# smps_v_1_3.net
KiCad netlist of a schematic drawn in EAGLE
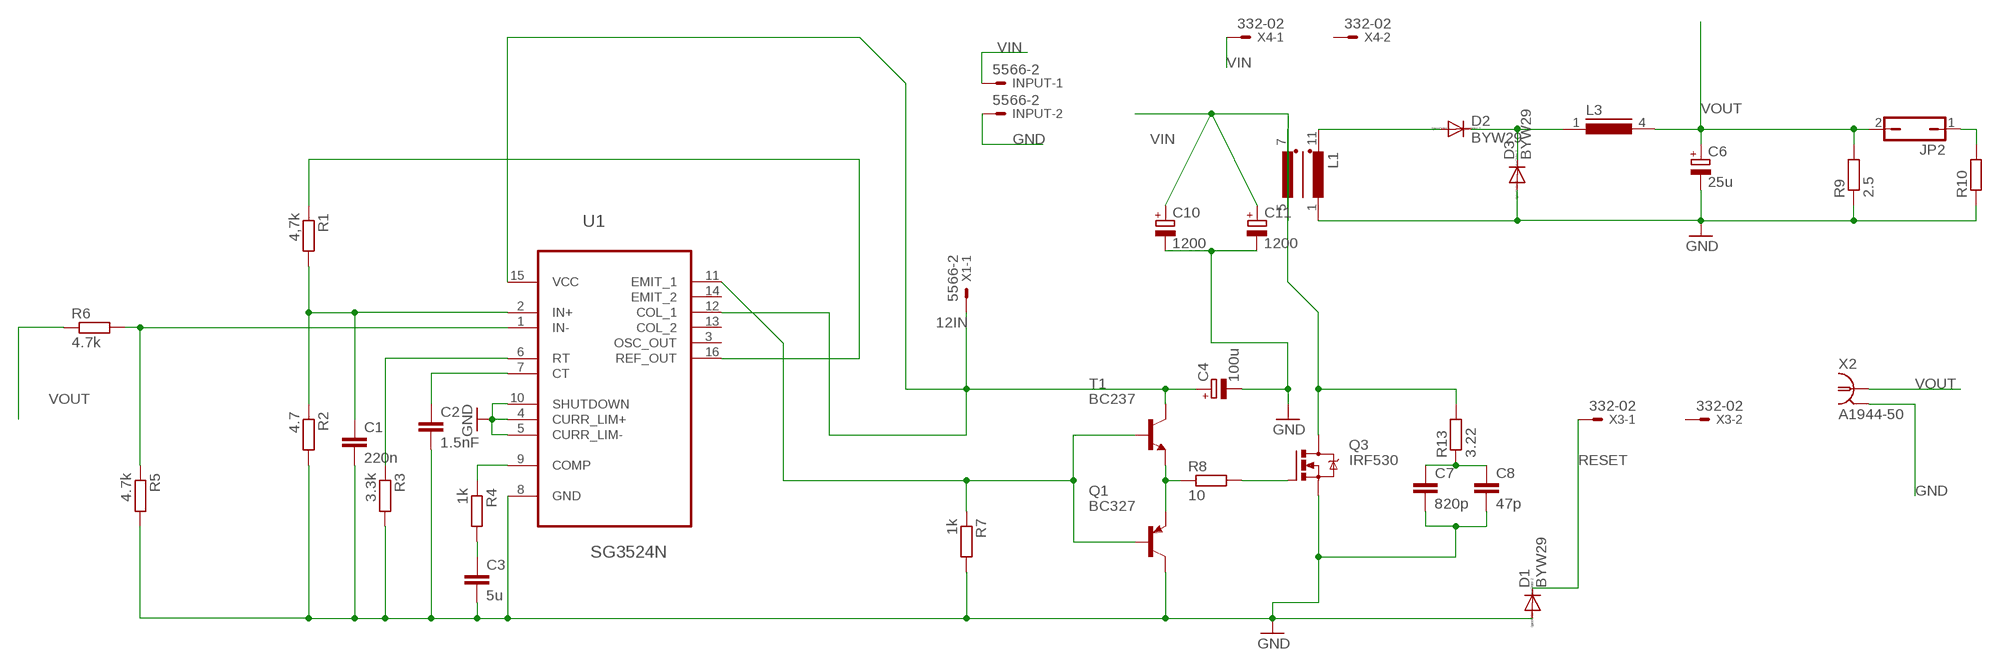
[diagram p0: schematic, sheet 1]

(export (version "E")
  (design (tool "Eeschema 10.0.6"))
  (components
    (comp (ref "C1")
      (value "220n")
      (footprint "eagle-import:C050-030X075")
      (libsource (lib "eagle-import") (part "resistor_C-EU050-030X075"))
    )
    (comp (ref "C2")
      (value "1.5nF")
      (footprint "eagle-import:C050-035X075")
      (libsource (lib "eagle-import") (part "C-EU050-035X075"))
    )
    (comp (ref "C3")
      (value "5u")
      (footprint "eagle-import:C050-035X075")
      (libsource (lib "eagle-import") (part "C-EU050-035X075"))
    )
    (comp (ref "C4")
      (value "100u")
      (footprint "eagle-import:E3,5-8")
      (libsource (lib "eagle-import") (part "CPOL-EUE3.5-8"))
    )
    (comp (ref "C6")
      (value "25u")
      (footprint "eagle-import:E3,5-8")
      (libsource (lib "eagle-import") (part "CPOL-EUE3.5-8"))
    )
    (comp (ref "C7")
      (value "820p")
      (footprint "eagle-import:C050-030X075")
      (libsource (lib "eagle-import") (part "C-EU050-030X075"))
    )
    (comp (ref "C8")
      (value "47p")
      (footprint "eagle-import:C050-030X075")
      (libsource (lib "eagle-import") (part "C-EU050-030X075"))
    )
    (comp (ref "C10")
      (value "1200")
      (footprint "eagle-import:E7,5-16")
      (libsource (lib "eagle-import") (part "CPOL-EUE7.5-16"))
    )
    (comp (ref "C11")
      (value "1200")
      (footprint "eagle-import:E7,5-16")
      (libsource (lib "eagle-import") (part "CPOL-EUE7.5-16"))
    )
    (comp (ref "D1")
      (value "BYW29")
      (footprint "eagle-import:DO220S")
      (libsource (lib "eagle-import") (part "BYW29"))
    )
    (comp (ref "D2")
      (value "BYW29")
      (footprint "eagle-import:DO220S")
      (libsource (lib "eagle-import") (part "BYW29"))
    )
    (comp (ref "D3")
      (value "BYW29")
      (footprint "eagle-import:DO220S")
      (libsource (lib "eagle-import") (part "BYW29"))
    )
    (comp (ref "INPUT")
      (value "5566-2")
      (footprint "eagle-import:5566-2")
      (libsource (lib "eagle-import") (part "5566-2"))
    )
    (comp (ref "JP2")
      (value "JP1Q")
      (footprint "eagle-import:JP1")
      (libsource (lib "eagle-import") (part "JP1Q"))
    )
    (comp (ref "L1")
      (value "RM6-2RM812")
      (footprint "eagle-import:RM8-12")
      (libsource (lib "eagle-import") (part "RM6-2RM812"))
    )
    (comp (ref "L3")
      (value "RM6NEWVARIANT")
      (footprint "eagle-import:RM7-8")
      (libsource (lib "eagle-import") (part "RM6NEWVARIANT"))
    )
    (comp (ref "Q1")
      (value "BC327")
      (footprint "eagle-import:TO92")
      (libsource (lib "eagle-import") (part "BC327"))
    )
    (comp (ref "Q3")
      (value "IRF530")
      (footprint "eagle-import:TO220BV")
      (libsource (lib "eagle-import") (part "IRF530"))
    )
    (comp (ref "R1")
      (value "4,7k")
      (footprint "eagle-import:0204_7")
      (libsource (lib "eagle-import") (part "resistor_R-EU_0204/7"))
    )
    (comp (ref "R2")
      (value "4.7")
      (footprint "eagle-import:0204_7")
      (libsource (lib "eagle-import") (part "resistor_R-EU_0204/7"))
    )
    (comp (ref "R3")
      (value "3.3k")
      (footprint "eagle-import:0204_7")
      (libsource (lib "eagle-import") (part "resistor_R-EU_0204/7"))
    )
    (comp (ref "R4")
      (value "1k")
      (footprint "eagle-import:0204_7")
      (libsource (lib "eagle-import") (part "resistor_R-EU_0204/7"))
    )
    (comp (ref "R5")
      (value "4.7k")
      (footprint "eagle-import:0204_7")
      (libsource (lib "eagle-import") (part "resistor_R-EU_0204/7"))
    )
    (comp (ref "R6")
      (value "4.7k")
      (footprint "eagle-import:0204_7")
      (libsource (lib "eagle-import") (part "resistor_R-EU_0204/7"))
    )
    (comp (ref "R7")
      (value "1k")
      (footprint "eagle-import:0204_7")
      (libsource (lib "eagle-import") (part "resistor_R-EU_0204/7"))
    )
    (comp (ref "R8")
      (value "10")
      (footprint "eagle-import:0204_7")
      (libsource (lib "eagle-import") (part "resistor_R-EU_0204/7"))
    )
    (comp (ref "R9")
      (value "2.5")
      (footprint "eagle-import:0617V")
      (libsource (lib "eagle-import") (part "R-EU_0617/5V"))
    )
    (comp (ref "R10")
      (value "R-EU_0617/5V")
      (footprint "eagle-import:0617V")
      (libsource (lib "eagle-import") (part "R-EU_0617/5V"))
    )
    (comp (ref "R13")
      (value "3.22")
      (footprint "eagle-import:0204V")
      (libsource (lib "eagle-import") (part "R-EU_0204/2V"))
    )
    (comp (ref "T1")
      (value "BC237")
      (footprint "eagle-import:TO92")
      (libsource (lib "eagle-import") (part "BC237"))
    )
    (comp (ref "U1")
      (value "SG3524N")
      (footprint "eagle-import:DIP254P762X508-16")
      (libsource (lib "eagle-import") (part "SG3524N"))
    )
    (comp (ref "X1")
      (value "5566-2")
      (footprint "eagle-import:5566-2")
      (libsource (lib "eagle-import") (part "5566-2"))
    )
    (comp (ref "X2")
      (value "A1944-50")
      (footprint "eagle-import:A1944")
      (libsource (lib "eagle-import") (part "A1944-50"))
    )
    (comp (ref "X3")
      (value "332-02")
      (footprint "eagle-import:332-02")
      (libsource (lib "eagle-import") (part "332-02"))
    )
    (comp (ref "X4")
      (value "332-02")
      (footprint "eagle-import:332-02")
      (libsource (lib "eagle-import") (part "332-02"))
    )
  )
  (nets
    (net (code "1") (name "/12IN") (class "Default")
      (node (ref "C4") (pin "+") (pinfunction "+_+") (pintype "passive"))
      (node (ref "T1") (pin "3") (pinfunction "C_3") (pintype "passive"))
      (node (ref "U1") (pin "12") (pinfunction "COL_1_12") (pintype "passive"))
      (node (ref "U1") (pin "15") (pinfunction "VCC_15") (pintype "power_in"))
      (node (ref "X1") (pin "1") (pinfunction "S_1") (pintype "passive"))
    )
    (net (code "2") (name "/RESET") (class "Default")
      (node (ref "D1") (pin "C") (pinfunction "C_C") (pintype "passive"))
      (node (ref "X3") (pin "1") (pinfunction "S_1") (pintype "passive"))
    )
    (net (code "3") (name "/VIN") (class "Default")
      (node (ref "C10") (pin "+") (pinfunction "+_+") (pintype "passive"))
      (node (ref "C11") (pin "+") (pinfunction "+_+") (pintype "passive"))
      (node (ref "INPUT") (pin "1") (pinfunction "S_1") (pintype "passive"))
      (node (ref "L1") (pin "5") (pinfunction "W2E_5") (pintype "passive"))
      (node (ref "X4") (pin "1") (pinfunction "S_1") (pintype "passive"))
    )
    (net (code "4") (name "/VOUT") (class "Default")
      (node (ref "C6") (pin "+") (pinfunction "+_+") (pintype "passive"))
      (node (ref "JP2") (pin "2") (pinfunction "2_2") (pintype "passive"))
      (node (ref "L3") (pin "4") (pinfunction "2_4") (pintype "passive"))
      (node (ref "R6") (pin "1") (pinfunction "1_1") (pintype "passive"))
      (node (ref "R9") (pin "2") (pinfunction "2_2") (pintype "passive"))
      (node (ref "X2") (pin "1") (pinfunction "1_1") (pintype "passive"))
    )
    (net (code "5") (name "GND") (class "Default")
      (node (ref "C1") (pin "2") (pinfunction "2_2") (pintype "passive"))
      (node (ref "C10") (pin "-") (pinfunction "-_-") (pintype "passive"))
      (node (ref "C11") (pin "-") (pinfunction "-_-") (pintype "passive"))
      (node (ref "C2") (pin "2") (pinfunction "2_2") (pintype "passive"))
      (node (ref "C3") (pin "2") (pinfunction "2_2") (pintype "passive"))
      (node (ref "C4") (pin "-") (pinfunction "-_-") (pintype "passive"))
      (node (ref "C6") (pin "-") (pinfunction "-_-") (pintype "passive"))
      (node (ref "C7") (pin "2") (pinfunction "2_2") (pintype "passive"))
      (node (ref "C8") (pin "2") (pinfunction "2_2") (pintype "passive"))
      (node (ref "D1") (pin "A") (pinfunction "A_A") (pintype "passive"))
      (node (ref "D3") (pin "A") (pinfunction "A_A") (pintype "passive"))
      (node (ref "INPUT") (pin "2") (pinfunction "S_2") (pintype "passive"))
      (node (ref "L1") (pin "1") (pinfunction "W1E_1") (pintype "passive"))
      (node (ref "Q1") (pin "3") (pinfunction "C_3") (pintype "passive"))
      (node (ref "Q3") (pin "S") (pinfunction "S_S") (pintype "passive"))
      (node (ref "R10") (pin "1") (pinfunction "1_1") (pintype "passive"))
      (node (ref "R2") (pin "2") (pinfunction "2_2") (pintype "passive"))
      (node (ref "R3") (pin "2") (pinfunction "2_2") (pintype "passive"))
      (node (ref "R5") (pin "2") (pinfunction "2_2") (pintype "passive"))
      (node (ref "R7") (pin "2") (pinfunction "2_2") (pintype "passive"))
      (node (ref "R9") (pin "1") (pinfunction "1_1") (pintype "passive"))
      (node (ref "U1") (pin "10") (pinfunction "SHUTDOWN_10") (pintype "input"))
      (node (ref "U1") (pin "4") (pinfunction "CURR_LIM+_4") (pintype "input"))
      (node (ref "U1") (pin "5") (pinfunction "CURR_LIM-_5") (pintype "input"))
      (node (ref "U1") (pin "8") (pinfunction "GND_8") (pintype "passive"))
      (node (ref "X2") (pin "2") (pinfunction "2_2") (pintype "passive"))
      (node (ref "X2") (pin "3") (pinfunction "2_3") (pintype "passive"))
      (node (ref "X2") (pin "4") (pinfunction "2_4") (pintype "passive"))
      (node (ref "X2") (pin "5") (pinfunction "2_5") (pintype "passive"))
    )
    (net (code "6") (name "Net-(C3-Pad1)") (class "Default")
      (node (ref "C3") (pin "1") (pinfunction "1_1") (pintype "passive"))
      (node (ref "R4") (pin "2") (pinfunction "2_2") (pintype "passive"))
    )
    (net (code "7") (name "Net-(C7-Pad1)") (class "Default")
      (node (ref "C7") (pin "1") (pinfunction "1_1") (pintype "passive"))
      (node (ref "C8") (pin "1") (pinfunction "1_1") (pintype "passive"))
      (node (ref "R13") (pin "1") (pinfunction "1_1") (pintype "passive"))
    )
    (net (code "8") (name "Net-(D2-PadC)") (class "Default")
      (node (ref "D2") (pin "C") (pinfunction "C_C") (pintype "passive"))
      (node (ref "D3") (pin "C") (pinfunction "C_C") (pintype "passive"))
      (node (ref "L3") (pin "1") (pinfunction "1_1") (pintype "passive"))
    )
    (net (code "9") (name "Net-(JP2-Pad1)") (class "Default")
      (node (ref "JP2") (pin "1") (pinfunction "1_1") (pintype "passive"))
      (node (ref "R10") (pin "2") (pinfunction "2_2") (pintype "passive"))
    )
    (net (code "10") (name "Net-(L1-W1A)") (class "Default")
      (node (ref "D2") (pin "A") (pinfunction "A_A") (pintype "passive"))
      (node (ref "L1") (pin "11") (pinfunction "W1A_11") (pintype "passive"))
    )
    (net (code "11") (name "Net-(L1-W2A)") (class "Default")
      (node (ref "L1") (pin "7") (pinfunction "W2A_7") (pintype "passive"))
      (node (ref "Q3") (pin "D") (pinfunction "D_D") (pintype "passive"))
      (node (ref "R13") (pin "2") (pinfunction "2_2") (pintype "passive"))
    )
    (net (code "12") (name "Net-(Q1-B)") (class "Default")
      (node (ref "Q1") (pin "2") (pinfunction "B_2") (pintype "passive"))
      (node (ref "R7") (pin "1") (pinfunction "1_1") (pintype "passive"))
      (node (ref "T1") (pin "2") (pinfunction "B_2") (pintype "passive"))
      (node (ref "U1") (pin "11") (pinfunction "EMIT_1_11") (pintype "passive"))
    )
    (net (code "13") (name "Net-(Q1-E)") (class "Default")
      (node (ref "Q1") (pin "1") (pinfunction "E_1") (pintype "passive"))
      (node (ref "R8") (pin "1") (pinfunction "1_1") (pintype "passive"))
      (node (ref "T1") (pin "1") (pinfunction "E_1") (pintype "passive"))
    )
    (net (code "14") (name "Net-(Q3-PadG)") (class "Default")
      (node (ref "Q3") (pin "G") (pinfunction "G_G") (pintype "passive"))
      (node (ref "R8") (pin "2") (pinfunction "2_2") (pintype "passive"))
    )
    (net (code "15") (name "Net-(U1-COMP)") (class "Default")
      (node (ref "R4") (pin "1") (pinfunction "1_1") (pintype "passive"))
      (node (ref "U1") (pin "9") (pinfunction "COMP_9") (pintype "passive"))
    )
    (net (code "16") (name "Net-(U1-CT)") (class "Default")
      (node (ref "C2") (pin "1") (pinfunction "1_1") (pintype "passive"))
      (node (ref "U1") (pin "7") (pinfunction "CT_7") (pintype "input"))
    )
    (net (code "17") (name "Net-(U1-IN+)") (class "Default")
      (node (ref "C1") (pin "1") (pinfunction "1_1") (pintype "passive"))
      (node (ref "R1") (pin "2") (pinfunction "2_2") (pintype "passive"))
      (node (ref "R2") (pin "1") (pinfunction "1_1") (pintype "passive"))
      (node (ref "U1") (pin "2") (pinfunction "IN+_2") (pintype "input"))
    )
    (net (code "18") (name "Net-(U1-IN-)") (class "Default")
      (node (ref "R5") (pin "1") (pinfunction "1_1") (pintype "passive"))
      (node (ref "R6") (pin "2") (pinfunction "2_2") (pintype "passive"))
      (node (ref "U1") (pin "1") (pinfunction "IN-_1") (pintype "input"))
    )
    (net (code "19") (name "Net-(U1-REF_OUT)") (class "Default")
      (node (ref "R1") (pin "1") (pinfunction "1_1") (pintype "passive"))
      (node (ref "U1") (pin "16") (pinfunction "REF_OUT_16") (pintype "output"))
    )
    (net (code "20") (name "Net-(U1-RT)") (class "Default")
      (node (ref "R3") (pin "1") (pinfunction "1_1") (pintype "passive"))
      (node (ref "U1") (pin "6") (pinfunction "RT_6") (pintype "input"))
    )
    (net (code "21") (name "unconnected-(U1-COL_2-Pad13)") (class "Default")
      (node (ref "U1") (pin "13") (pinfunction "COL_2_13") (pintype "passive"))
    )
    (net (code "22") (name "unconnected-(U1-EMIT_2-Pad14)") (class "Default")
      (node (ref "U1") (pin "14") (pinfunction "EMIT_2_14") (pintype "passive"))
    )
    (net (code "23") (name "unconnected-(U1-OSC_OUT-Pad3)") (class "Default")
      (node (ref "U1") (pin "3") (pinfunction "OSC_OUT_3") (pintype "output"))
    )
    (net (code "24") (name "unconnected-(X3B-S-Pad2)") (class "Default")
      (node (ref "X3") (pin "2") (pinfunction "S_2") (pintype "passive"))
    )
    (net (code "25") (name "unconnected-(X4B-S-Pad2)") (class "Default")
      (node (ref "X4") (pin "2") (pinfunction "S_2") (pintype "passive"))
    )
  )
)
